# USB.net
KiCad netlist of a schematic drawn in Altium Designer
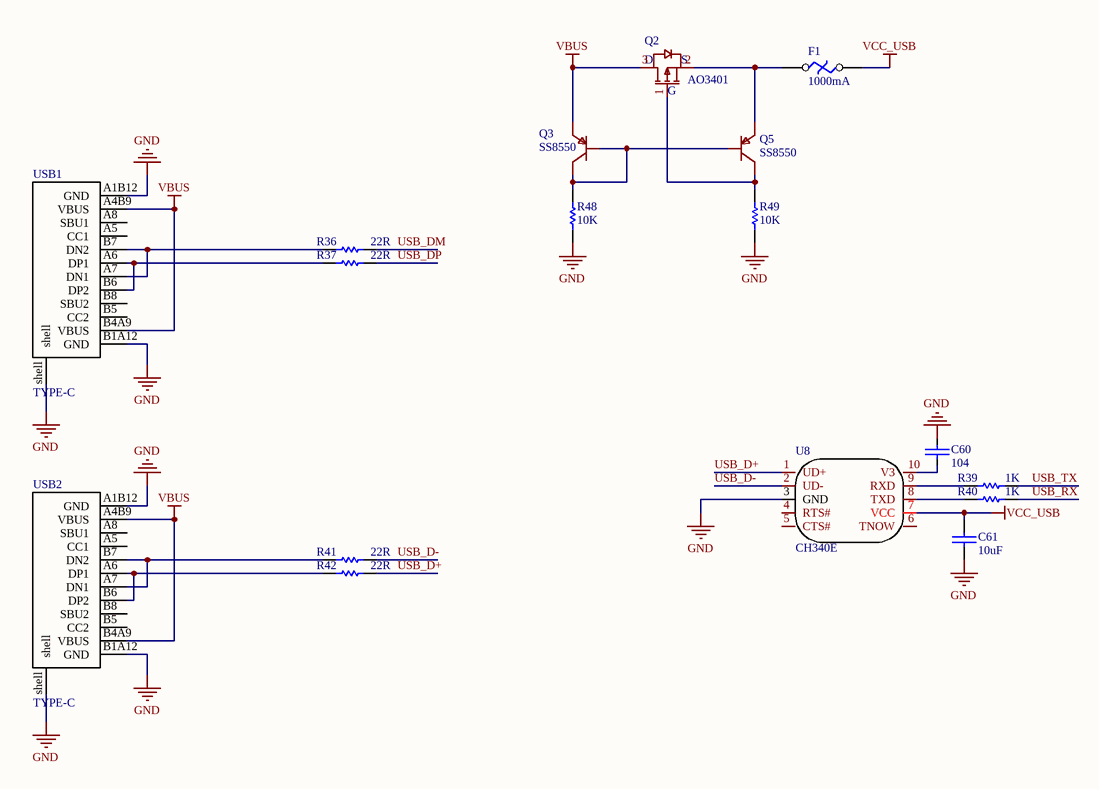
[diagram p0: USB.SchDoc]

(export (version "E")
  (design (tool "Eeschema 10.0.6"))
  (components
    (comp (ref "C60")
      (value "104")
      (footprint "C 0603")
      (description "Capacitor")
      (libsource (lib "") (part "CAP_1"))
    )
    (comp (ref "C61")
      (value "10uF")
      (footprint "C 0603")
      (description "Capacitor")
      (libsource (lib "*") (part "CAP"))
    )
    (comp (ref "F1")
      (value "1000mA")
      (footprint "F 0805")
      (description "熔断开关")
      (libsource (lib "松鼠GUI原理图库") (part "F"))
    )
    (comp (ref "Q2") (value "AO3401") (footprint "SOT-23") (libsource (lib "Sheet") (part "PMOS")))
    (comp (ref "Q3") (value "SS8550") (footprint "SOT-23") (libsource (lib "Sheet") (part "PNP")))
    (comp (ref "Q5") (value "SS8550") (footprint "SOT-23") (libsource (lib "Sheet") (part "PNP")))
    (comp (ref "R36") (value "22R") (footprint "R 0603") (libsource (lib "Sheet") (part "RES")))
    (comp (ref "R37") (value "22R") (footprint "R 0603") (libsource (lib "Sheet") (part "RES")))
    (comp (ref "R39") (value "1K") (footprint "R 0603") (libsource (lib "Sheet") (part "RES")))
    (comp (ref "R40") (value "1K") (footprint "R 0603") (libsource (lib "Sheet") (part "RES")))
    (comp (ref "R41") (value "22R") (footprint "R 0603") (libsource (lib "Sheet") (part "RES")))
    (comp (ref "R42") (value "22R") (footprint "R 0603") (libsource (lib "Sheet") (part "RES")))
    (comp (ref "R48") (value "10K") (footprint "R 0603") (libsource (lib "Sheet") (part "RES")))
    (comp (ref "R49") (value "10K") (footprint "R 0603") (libsource (lib "Sheet") (part "RES")))
    (comp (ref "U8") (value "CH340E") (footprint "MSOP-10") (libsource (lib "Sheet") (part "CH340E")))
    (comp (ref "USB1")
      (value "TYPE-C")
      (footprint "USB-TYPE-C")
      (description "TYPE-C 16pin")
      (libsource (lib "Sheet") (part "USB TYPE-C"))
    )
    (comp (ref "USB2")
      (value "TYPE-C")
      (footprint "USB-TYPE-C")
      (description "TYPE-C 16pin")
      (libsource (lib "Sheet") (part "USB TYPE-C"))
    )
  )
  (nets
    (net (code "1") (name "/USB_D+") (class "Default")
      (node (ref "R42") (pin "2") (pinfunction "2_2") (pintype "passive"))
      (node (ref "U8") (pin "1") (pinfunction "UD+_1") (pintype "passive"))
    )
    (net (code "2") (name "/USB_D-") (class "Default")
      (node (ref "R41") (pin "2") (pinfunction "2_2") (pintype "passive"))
      (node (ref "U8") (pin "2") (pinfunction "UD-_2") (pintype "passive"))
    )
    (net (code "3") (name "/USB_DM") (class "Default")
      (node (ref "R36") (pin "2") (pinfunction "2_2") (pintype "passive"))
    )
    (net (code "4") (name "/USB_DP") (class "Default")
      (node (ref "R37") (pin "2") (pinfunction "2_2") (pintype "passive"))
    )
    (net (code "5") (name "/USB_RX") (class "Default")
      (node (ref "R40") (pin "2") (pinfunction "2_2") (pintype "passive"))
    )
    (net (code "6") (name "/USB_TX") (class "Default")
      (node (ref "R39") (pin "2") (pinfunction "2_2") (pintype "passive"))
    )
    (net (code "7") (name "GND") (class "Default")
      (node (ref "C60") (pin "1") (pinfunction "1_1") (pintype "passive"))
      (node (ref "C61") (pin "2") (pinfunction "2_2") (pintype "passive"))
      (node (ref "R48") (pin "1") (pinfunction "1_1") (pintype "passive"))
      (node (ref "R49") (pin "1") (pinfunction "1_1") (pintype "passive"))
      (node (ref "U8") (pin "3") (pinfunction "GND_3") (pintype "passive"))
      (node (ref "USB1") (pin "A1B12") (pinfunction "GND_A1B12") (pintype "passive"))
      (node (ref "USB1") (pin "B1A12") (pinfunction "GND_B1A12") (pintype "passive"))
      (node (ref "USB1") (pin "shell") (pinfunction "shell_shell") (pintype "passive"))
      (node (ref "USB2") (pin "A1B12") (pinfunction "GND_A1B12") (pintype "passive"))
      (node (ref "USB2") (pin "B1A12") (pinfunction "GND_B1A12") (pintype "passive"))
      (node (ref "USB2") (pin "shell") (pinfunction "shell_shell") (pintype "passive"))
    )
    (net (code "8") (name "Net-(Q2-G)") (class "Default")
      (node (ref "Q2") (pin "1") (pinfunction "G_1") (pintype "passive"))
      (node (ref "Q5") (pin "3") (pinfunction "C_3") (pintype "passive"))
      (node (ref "R49") (pin "2") (pinfunction "2_2") (pintype "passive"))
    )
    (net (code "9") (name "Net-(Q2-S)") (class "Default")
      (node (ref "F1") (pin "1") (pinfunction "1_1") (pintype "passive"))
      (node (ref "Q2") (pin "2") (pinfunction "S_2") (pintype "passive"))
      (node (ref "Q5") (pin "2") (pinfunction "E_2") (pintype "passive"))
    )
    (net (code "10") (name "Net-(Q3-B)") (class "Default")
      (node (ref "Q3") (pin "1") (pinfunction "B_1") (pintype "passive"))
      (node (ref "Q3") (pin "3") (pinfunction "C_3") (pintype "passive"))
      (node (ref "Q5") (pin "1") (pinfunction "B_1") (pintype "passive"))
      (node (ref "R48") (pin "2") (pinfunction "2_2") (pintype "passive"))
    )
    (net (code "11") (name "Net-(U8-RXD)") (class "Default")
      (node (ref "R39") (pin "1") (pinfunction "1_1") (pintype "passive"))
      (node (ref "U8") (pin "9") (pinfunction "RXD_9") (pintype "passive"))
    )
    (net (code "12") (name "Net-(U8-TXD)") (class "Default")
      (node (ref "R40") (pin "1") (pinfunction "1_1") (pintype "passive"))
      (node (ref "U8") (pin "8") (pinfunction "TXD_8") (pintype "passive"))
    )
    (net (code "13") (name "Net-(U8-V3)") (class "Default")
      (node (ref "C60") (pin "2") (pinfunction "2_2") (pintype "passive"))
      (node (ref "U8") (pin "10") (pinfunction "V3_10") (pintype "passive"))
    )
    (net (code "14") (name "Net-(USB1-DN1)") (class "Default")
      (node (ref "R36") (pin "1") (pinfunction "1_1") (pintype "passive"))
      (node (ref "USB1") (pin "A7") (pinfunction "DN1_A7") (pintype "passive"))
      (node (ref "USB1") (pin "B7") (pinfunction "DN2_B7") (pintype "passive"))
    )
    (net (code "15") (name "Net-(USB1-DP1)") (class "Default")
      (node (ref "R37") (pin "1") (pinfunction "1_1") (pintype "passive"))
      (node (ref "USB1") (pin "A6") (pinfunction "DP1_A6") (pintype "passive"))
      (node (ref "USB1") (pin "B6") (pinfunction "DP2_B6") (pintype "passive"))
    )
    (net (code "16") (name "Net-(USB2-DN1)") (class "Default")
      (node (ref "R41") (pin "1") (pinfunction "1_1") (pintype "passive"))
      (node (ref "USB2") (pin "A7") (pinfunction "DN1_A7") (pintype "passive"))
      (node (ref "USB2") (pin "B7") (pinfunction "DN2_B7") (pintype "passive"))
    )
    (net (code "17") (name "Net-(USB2-DP1)") (class "Default")
      (node (ref "R42") (pin "1") (pinfunction "1_1") (pintype "passive"))
      (node (ref "USB2") (pin "A6") (pinfunction "DP1_A6") (pintype "passive"))
      (node (ref "USB2") (pin "B6") (pinfunction "DP2_B6") (pintype "passive"))
    )
    (net (code "18") (name "VBUS") (class "Default")
      (node (ref "Q2") (pin "3") (pinfunction "D_3") (pintype "passive"))
      (node (ref "Q3") (pin "2") (pinfunction "E_2") (pintype "passive"))
      (node (ref "USB1") (pin "A4B9") (pinfunction "VBUS_A4B9") (pintype "passive"))
      (node (ref "USB1") (pin "B4A9") (pinfunction "VBUS_B4A9") (pintype "passive"))
      (node (ref "USB2") (pin "A4B9") (pinfunction "VBUS_A4B9") (pintype "passive"))
      (node (ref "USB2") (pin "B4A9") (pinfunction "VBUS_B4A9") (pintype "passive"))
    )
    (net (code "19") (name "VCC_USB") (class "Default")
      (node (ref "C61") (pin "1") (pinfunction "1_1") (pintype "passive"))
      (node (ref "F1") (pin "2") (pinfunction "2_2") (pintype "passive"))
      (node (ref "U8") (pin "7") (pinfunction "VCC_7") (pintype "passive"))
    )
    (net (code "20") (name "unconnected-(U8-CTS#-Pad5)") (class "Default")
      (node (ref "U8") (pin "5") (pinfunction "CTS#_5") (pintype "passive"))
    )
    (net (code "21") (name "unconnected-(U8-RTS#-Pad4)") (class "Default")
      (node (ref "U8") (pin "4") (pinfunction "RTS#_4") (pintype "passive"))
    )
    (net (code "22") (name "unconnected-(U8-TNOW-Pad6)") (class "Default")
      (node (ref "U8") (pin "6") (pinfunction "TNOW_6") (pintype "passive"))
    )
    (net (code "23") (name "unconnected-(USB1-CC1-PadA5)") (class "Default")
      (node (ref "USB1") (pin "A5") (pinfunction "CC1_A5") (pintype "passive"))
    )
    (net (code "24") (name "unconnected-(USB1-CC2-PadB5)") (class "Default")
      (node (ref "USB1") (pin "B5") (pinfunction "CC2_B5") (pintype "passive"))
    )
    (net (code "25") (name "unconnected-(USB1-SBU1-PadA8)") (class "Default")
      (node (ref "USB1") (pin "A8") (pinfunction "SBU1_A8") (pintype "passive"))
    )
    (net (code "26") (name "unconnected-(USB1-SBU2-PadB8)") (class "Default")
      (node (ref "USB1") (pin "B8") (pinfunction "SBU2_B8") (pintype "passive"))
    )
    (net (code "27") (name "unconnected-(USB2-CC1-PadA5)") (class "Default")
      (node (ref "USB2") (pin "A5") (pinfunction "CC1_A5") (pintype "passive"))
    )
    (net (code "28") (name "unconnected-(USB2-CC2-PadB5)") (class "Default")
      (node (ref "USB2") (pin "B5") (pinfunction "CC2_B5") (pintype "passive"))
    )
    (net (code "29") (name "unconnected-(USB2-SBU1-PadA8)") (class "Default")
      (node (ref "USB2") (pin "A8") (pinfunction "SBU1_A8") (pintype "passive"))
    )
    (net (code "30") (name "unconnected-(USB2-SBU2-PadB8)") (class "Default")
      (node (ref "USB2") (pin "B8") (pinfunction "SBU2_B8") (pintype "passive"))
    )
  )
)
